# departure_board_controller.net
KiCad netlist of a schematic drawn in EasyEDA Pro
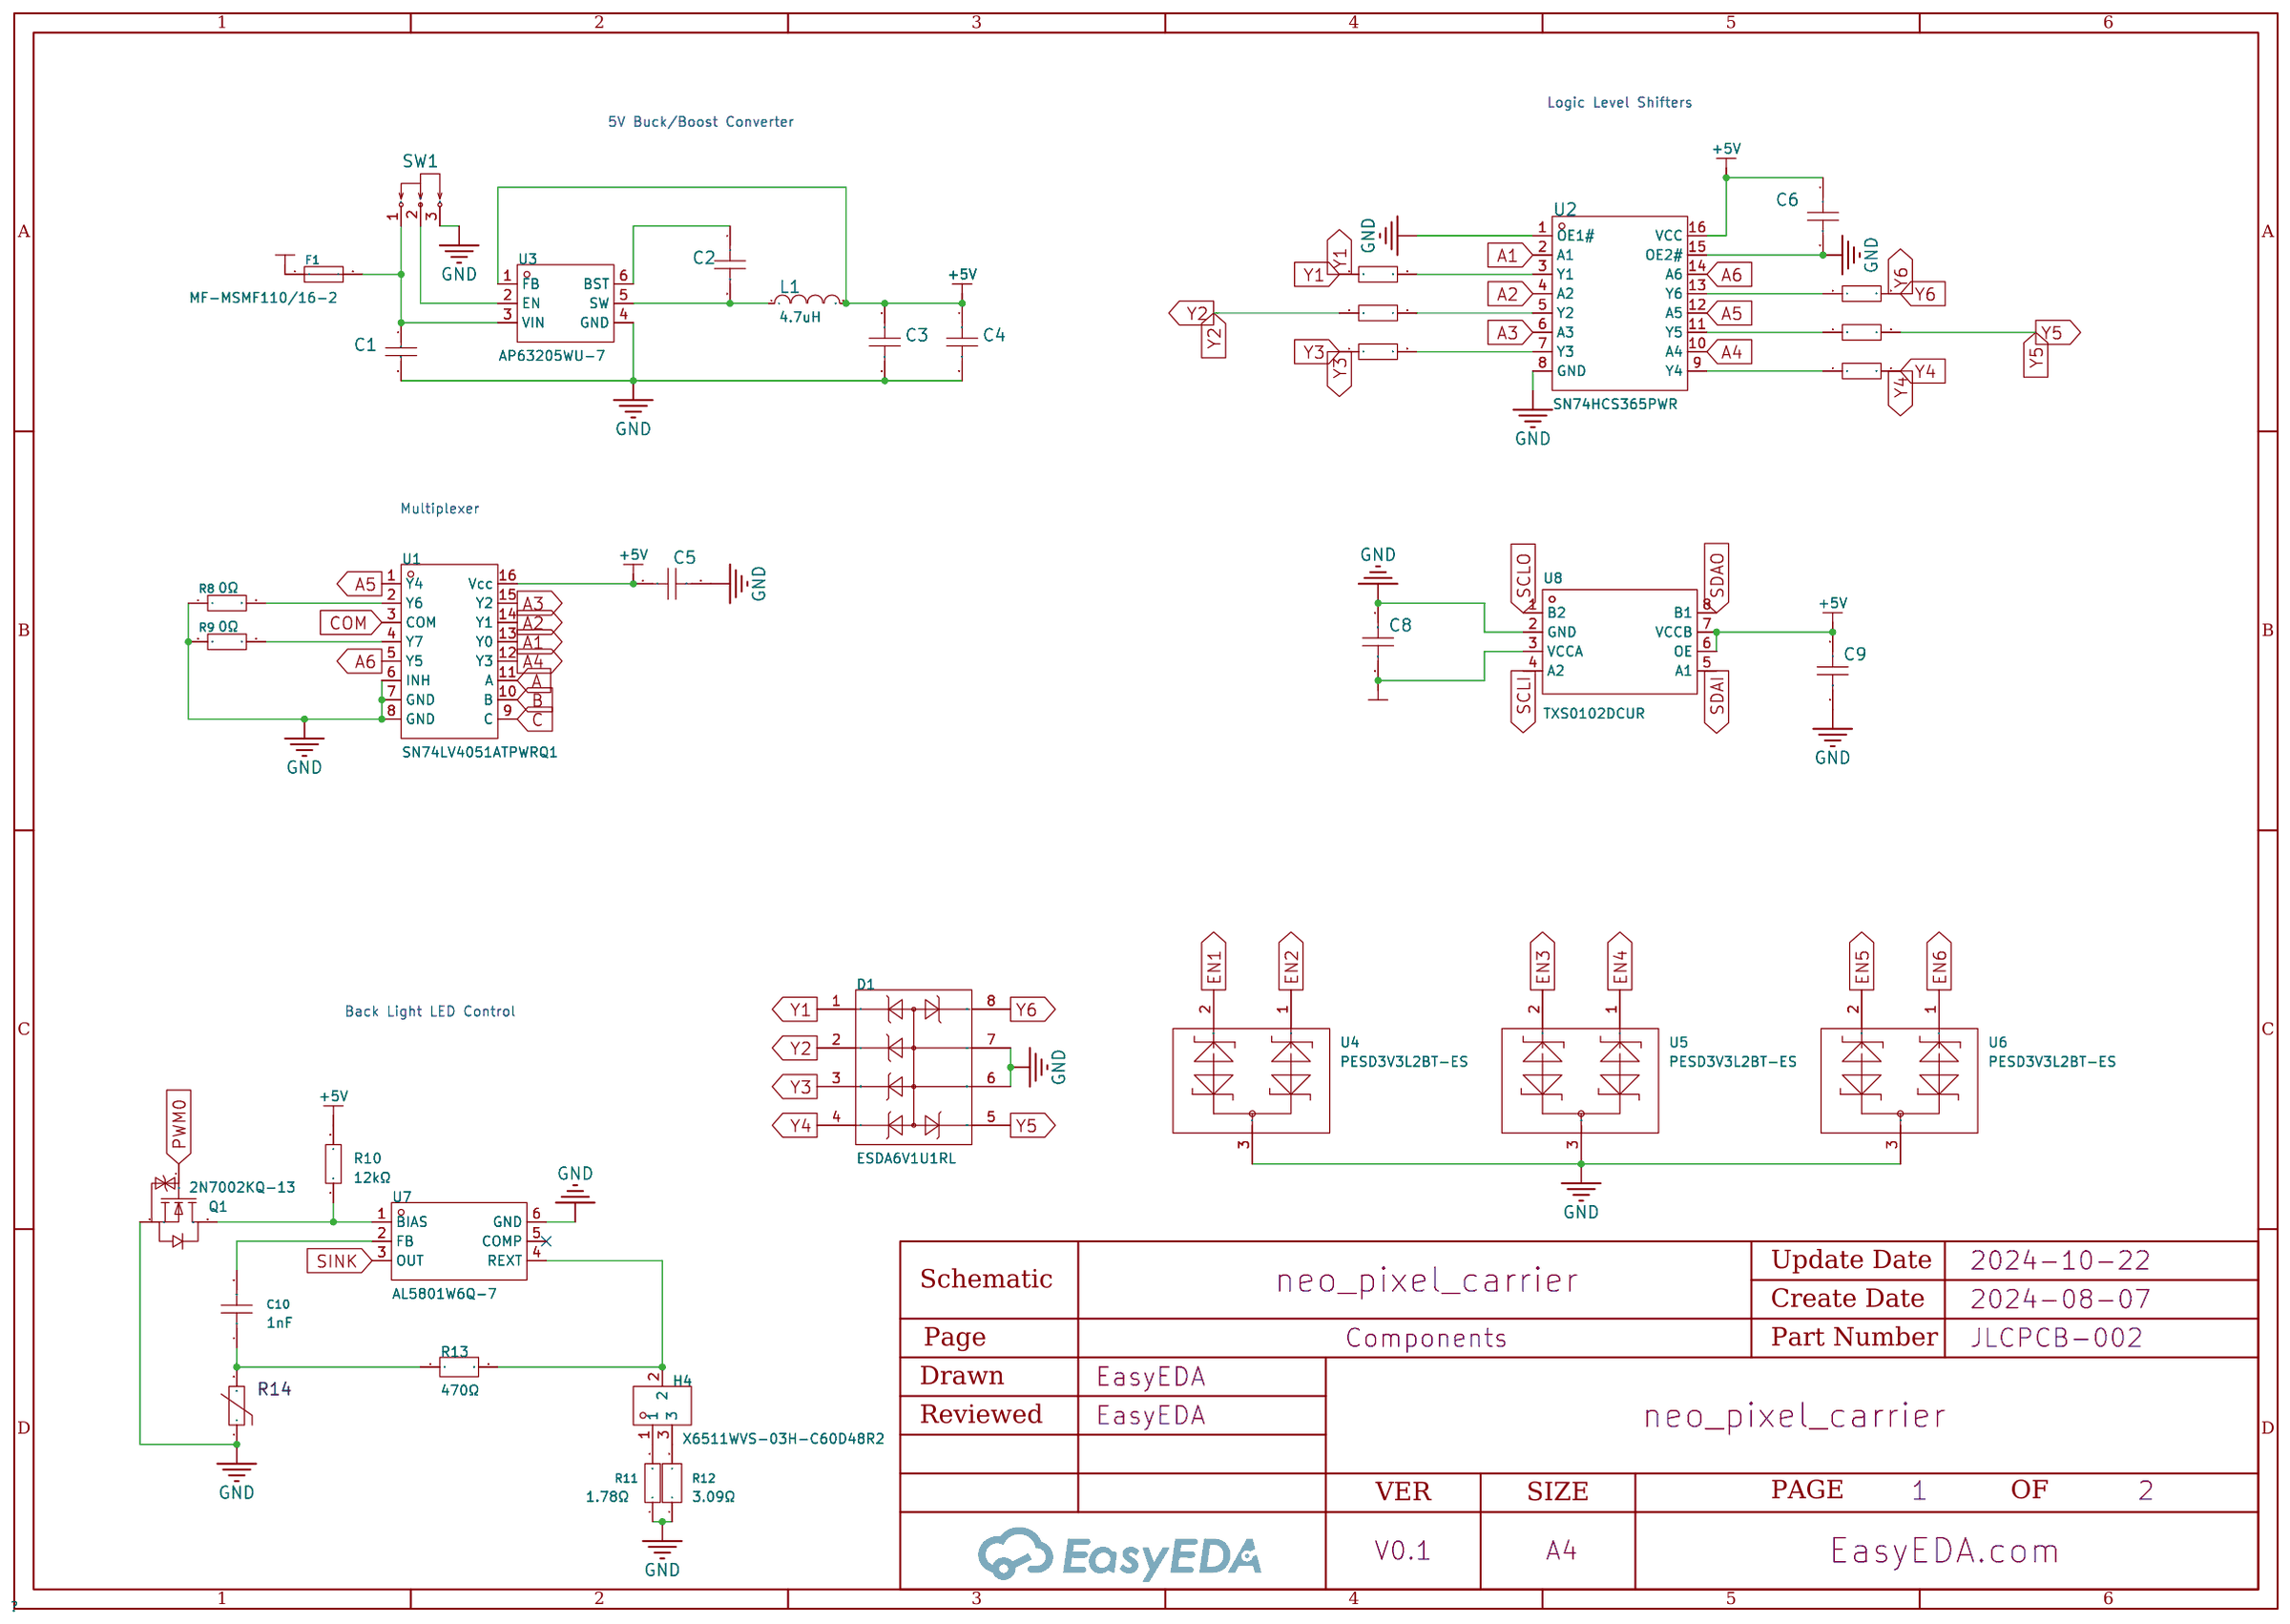
[diagram p0: Components]
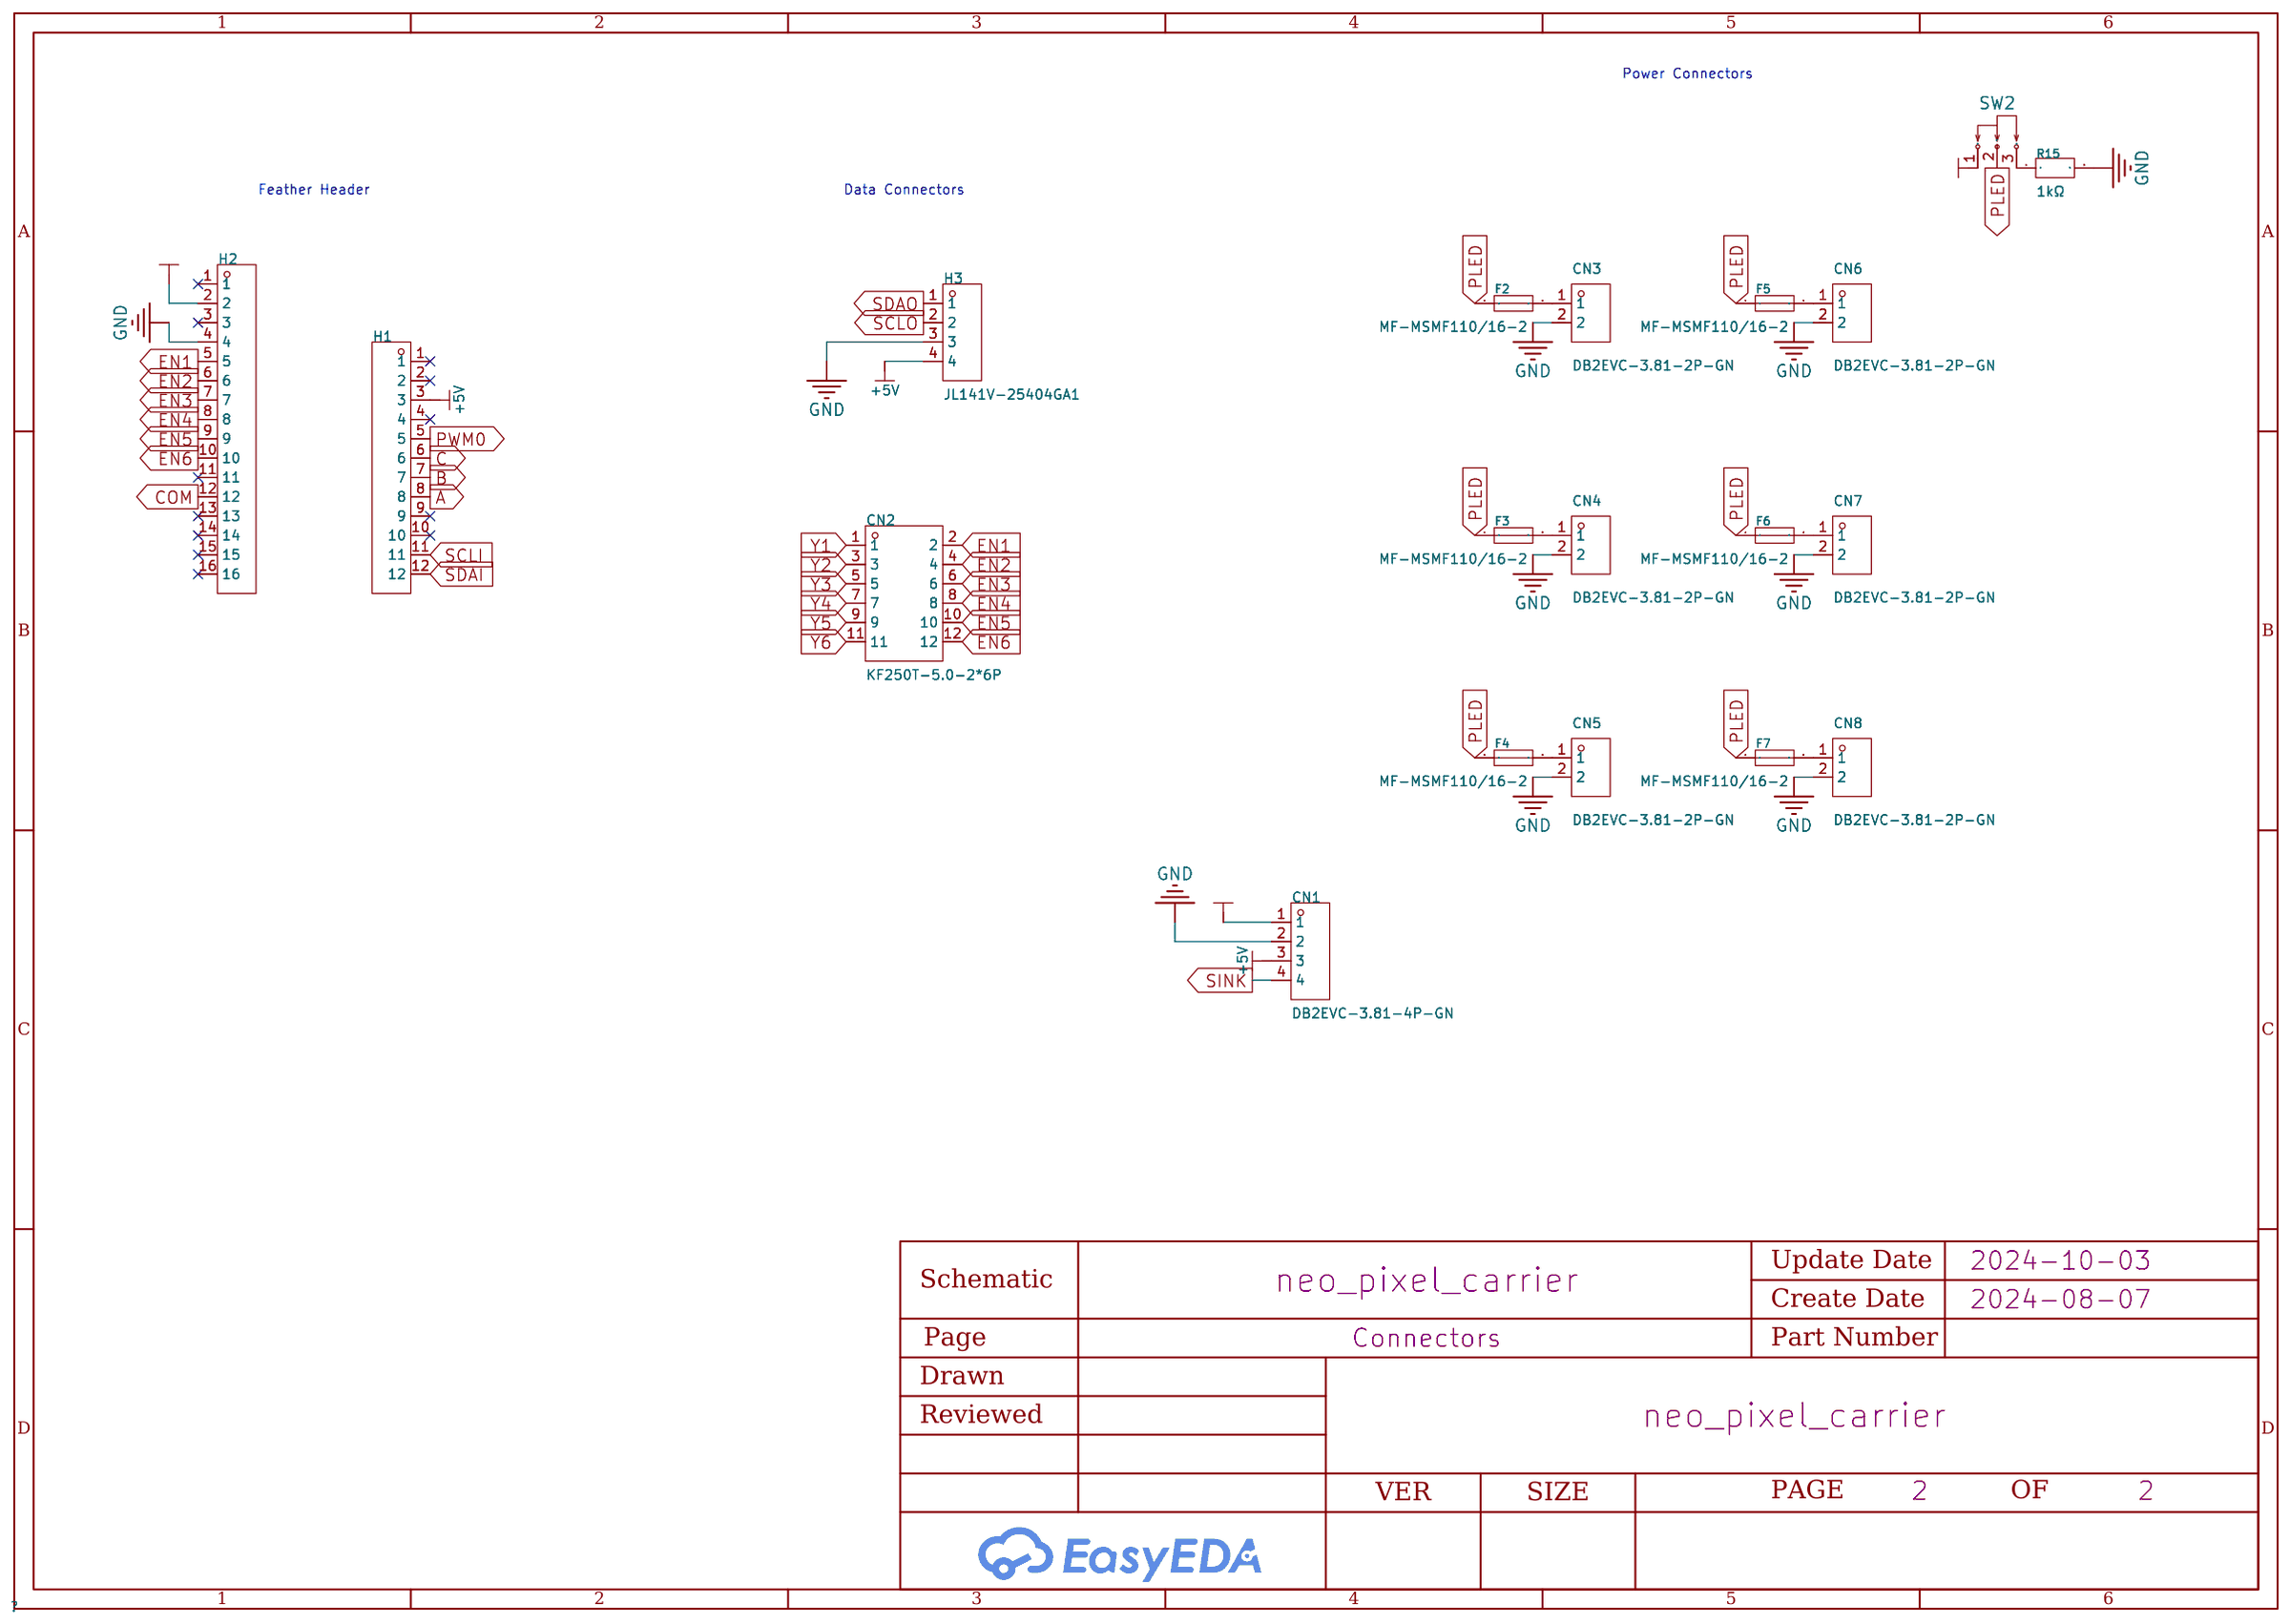
[diagram p1: Connectors]

(export (version "E")
  (design (tool "Eeschema 10.0.6"))
  (components
    (comp (ref "C1")
      (value "10uF")
      (footprint "easyedapro:C1210")
      (fields
        (field (name "Manufacturer Part") "CL32B106KAJNNNE")
        (field (name "Manufacturer") "SAMSUNG(三星)")
      )
      (libsource (lib "easyedapro") (part "CL32B106KAJNNNE"))
    )
    (comp (ref "C2")
      (value "100nF")
      (footprint "easyedapro:C1206")
      (fields (field (name "Manufacturer Part") "1206N104J500CT") (field (name "Manufacturer") "Walsin(华新科)"))
      (libsource (lib "easyedapro") (part "1206N104J500"))
    )
    (comp (ref "C3")
      (value "22uF")
      (footprint "easyedapro:C1210")
      (fields
        (field (name "Manufacturer Part") "CL32B226KAJNNNE")
        (field (name "Manufacturer") "SAMSUNG(三星)")
      )
      (libsource (lib "easyedapro") (part "CL32B226KAJNNNE"))
    )
    (comp (ref "C4")
      (value "22uF")
      (footprint "easyedapro:C1210")
      (fields
        (field (name "Manufacturer Part") "CL32B226KAJNNNE")
        (field (name "Manufacturer") "SAMSUNG(三星)")
      )
      (libsource (lib "easyedapro") (part "CL32B226KAJNNNE"))
    )
    (comp (ref "C5")
      (value "100nF")
      (footprint "easyedapro:C1206")
      (fields (field (name "Manufacturer Part") "1206N104J500CT") (field (name "Manufacturer") "Walsin(华新科)"))
      (libsource (lib "easyedapro") (part "1206N104J500"))
    )
    (comp (ref "C6")
      (value "100nF")
      (footprint "easyedapro:C1206")
      (fields (field (name "Manufacturer Part") "1206N104J500CT") (field (name "Manufacturer") "Walsin(华新科)"))
      (libsource (lib "easyedapro") (part "1206N104J500"))
    )
    (comp (ref "C8")
      (value "100nF")
      (footprint "easyedapro:C1206")
      (fields (field (name "Manufacturer Part") "1206N104J500CT") (field (name "Manufacturer") "Walsin(华新科)"))
      (libsource (lib "easyedapro") (part "1206N104J500"))
    )
    (comp (ref "C9")
      (value "100nF")
      (footprint "easyedapro:C1206")
      (fields (field (name "Manufacturer Part") "1206N104J500CT") (field (name "Manufacturer") "Walsin(华新科)"))
      (libsource (lib "easyedapro") (part "1206N104J500"))
    )
    (comp (ref "C10")
      (value "1nF")
      (footprint "easyedapro:C0402")
      (fields
        (field (name "Manufacturer Part") "GRM1555C1H102JA01D")
        (field (name "Manufacturer") "muRata(村田)")
      )
      (libsource (lib "easyedapro") (part "GRM1555C1H102JA01D"))
    )
    (comp (ref "D1")
      (value "ESDA6V1U1RL")
      (footprint "easyedapro:SO-8_L4.9-W3.9-P1.27-LS5.9-BL")
      (fields (field (name "Manufacturer") "ST(意法半导体)"))
      (libsource (lib "easyedapro") (part "ESDA6V1U1RL"))
    )
    (comp (ref "F1")
      (value "MF-MSMF110/16-2")
      (footprint "easyedapro:F1812")
      (fields (field (name "Manufacturer") "BOURNS"))
      (libsource (lib "easyedapro") (part "MF-MSMF110/16-2"))
    )
    (comp (ref "H4")
      (value "X6511WVS-03H-C60D48R2")
      (footprint "easyedapro:HDR-SMD_3P-P2.54_XKB_X6511WVS-03H-C60D48R2")
      (fields (field (name "Manufacturer") "XKB Connection(中国星坤)"))
      (libsource (lib "easyedapro") (part "X6511WVS-03H-C60D48R2"))
    )
    (comp (ref "L1")
      (value "4.7uH")
      (footprint "easyedapro:IND-SMD_L7.0-W7.0_CDRR7D45T125NP")
      (fields
        (field (name "Manufacturer Part") "CDRR7D45T125NP-4R7MC")
        (field (name "Manufacturer") "Sumida(胜美达)")
      )
      (libsource (lib "easyedapro") (part "CDRR7D45T125NP-4R7MC"))
    )
    (comp (ref "Q1")
      (value "2N7002KQ-13")
      (footprint "easyedapro:SOT-23-3_L2.9-W1.3-P1.90-LS2.4-BR")
      (fields (field (name "Manufacturer") "DIODES(美台)"))
      (libsource (lib "easyedapro") (part "2N7002KQ-13"))
    )
    (comp (ref "R1")
      (value "100Ω")
      (footprint "easyedapro:R0805")
      (fields (field (name "Manufacturer Part") "ERA6AEB101V") (field (name "Manufacturer") "PANASONIC(松下)"))
      (libsource (lib "easyedapro") (part "ERA6AEB101V"))
    )
    (comp (ref "R2")
      (value "100Ω")
      (footprint "easyedapro:R0805")
      (fields (field (name "Manufacturer Part") "ERA6AEB101V") (field (name "Manufacturer") "PANASONIC(松下)"))
      (libsource (lib "easyedapro") (part "ERA6AEB101V"))
    )
    (comp (ref "R3")
      (value "100Ω")
      (footprint "easyedapro:R0805")
      (fields (field (name "Manufacturer Part") "ERA6AEB101V") (field (name "Manufacturer") "PANASONIC(松下)"))
      (libsource (lib "easyedapro") (part "ERA6AEB101V"))
    )
    (comp (ref "R4")
      (value "100Ω")
      (footprint "easyedapro:R0805")
      (fields (field (name "Manufacturer Part") "ERA6AEB101V") (field (name "Manufacturer") "PANASONIC(松下)"))
      (libsource (lib "easyedapro") (part "ERA6AEB101V"))
    )
    (comp (ref "R5")
      (value "100Ω")
      (footprint "easyedapro:R0805")
      (fields (field (name "Manufacturer Part") "ERA6AEB101V") (field (name "Manufacturer") "PANASONIC(松下)"))
      (libsource (lib "easyedapro") (part "ERA6AEB101V"))
    )
    (comp (ref "R6")
      (value "100Ω")
      (footprint "easyedapro:R0805")
      (fields (field (name "Manufacturer Part") "ERA6AEB101V") (field (name "Manufacturer") "PANASONIC(松下)"))
      (libsource (lib "easyedapro") (part "ERA6AEB101V"))
    )
    (comp (ref "R8")
      (value "0Ω")
      (footprint "easyedapro:R0805")
      (fields (field (name "Manufacturer Part") "RTT050000FTP") (field (name "Manufacturer") "RALEC(旺诠)"))
      (libsource (lib "easyedapro") (part "RTT050000FTP"))
    )
    (comp (ref "R9")
      (value "0Ω")
      (footprint "easyedapro:R0805")
      (fields (field (name "Manufacturer Part") "RTT050000FTP") (field (name "Manufacturer") "RALEC(旺诠)"))
      (libsource (lib "easyedapro") (part "RTT050000FTP"))
    )
    (comp (ref "R10")
      (value "12kΩ")
      (footprint "easyedapro:R0805")
      (fields (field (name "Manufacturer Part") "PTFR0805B12K0N9") (field (name "Manufacturer") "RESI(开步睿思)"))
      (libsource (lib "easyedapro") (part "PTFR0805B12K0N9"))
    )
    (comp (ref "R11")
      (value "1.78Ω")
      (footprint "easyedapro:R0805")
      (fields
        (field (name "Manufacturer Part") "TR0805D1R78P0525")
        (field (name "Manufacturer") "EVER OHMS(天二科技)")
      )
      (libsource (lib "easyedapro") (part "TR0805D1R78P0525"))
    )
    (comp (ref "R12")
      (value "3.09Ω")
      (footprint "easyedapro:R0805")
      (fields (field (name "Manufacturer Part") "WR08W3R09FTL") (field (name "Manufacturer") "Walsin(华新科)"))
      (libsource (lib "easyedapro") (part "WR08W3R09FTL"))
    )
    (comp (ref "R13")
      (value "470Ω")
      (footprint "easyedapro:R0402")
      (fields (field (name "Manufacturer Part") "ERA2AEB471X") (field (name "Manufacturer") "PANASONIC(松下)"))
      (libsource (lib "easyedapro") (part "ERA2AEB471X"))
    )
    (comp (ref "R14")
      (value "10k")
      (footprint "easyedapro:R0805")
      (fields
        (field (name "Manufacturer Part") "KNTC0805/10KJ3450")
        (field (name "Manufacturer") "KUU")
        (field (name "Tolerance") "±0.5%")
      )
      (libsource (lib "easyedapro") (part "KNTC0805/10KJ3450"))
    )
    (comp (ref "SW1")
      (value "SS12D10G4 071")
      (footprint "easyedapro:SW-TH_SHOU-HAN_SS12D10G4")
      (fields (field (name "Manufacturer") "SHOU HAN(首韩)"))
      (libsource (lib "easyedapro") (part "SS12D10G4 071"))
    )
    (comp (ref "U1")
      (value "SN74LV4051ATPWRQ1")
      (footprint "easyedapro:TSSOP-16_L5.0-W4.4-P0.65-LS6.4-BL")
      (fields (field (name "Manufacturer") "TI(德州仪器)"))
      (libsource (lib "easyedapro") (part "SN74LV4051ATPWRQ1"))
    )
    (comp (ref "U2")
      (value "SN74HCS365PWR")
      (footprint "easyedapro:TSSOP-16_L5.0-W4.4-P0.65-LS6.4-BL")
      (fields (field (name "Manufacturer") "TI(德州仪器)"))
      (libsource (lib "easyedapro") (part "SN74HCS365PWR"))
    )
    (comp (ref "U3")
      (value "AP63205WU-7")
      (footprint "easyedapro:TSOT-23-6_L2.9-W1.6-P0.95-LS2.8-BL")
      (fields (field (name "Manufacturer") "DIODES(美台)"))
      (libsource (lib "easyedapro") (part "AP63205WU-7"))
    )
    (comp (ref "U4")
      (value "PESD3V3L2BT-ES")
      (footprint "easyedapro:SOT-23-3_L2.9-W1.3-P0.95-LS2.4-BR")
      (fields (field (name "Manufacturer") "ElecSuper(静芯微)"))
      (libsource (lib "easyedapro") (part "PESD3V3L2BT-ES"))
    )
    (comp (ref "U5")
      (value "PESD3V3L2BT-ES")
      (footprint "easyedapro:SOT-23-3_L2.9-W1.3-P0.95-LS2.4-BR")
      (fields (field (name "Manufacturer") "ElecSuper(静芯微)"))
      (libsource (lib "easyedapro") (part "PESD3V3L2BT-ES"))
    )
    (comp (ref "U6")
      (value "PESD3V3L2BT-ES")
      (footprint "easyedapro:SOT-23-3_L2.9-W1.3-P0.95-LS2.4-BR")
      (fields (field (name "Manufacturer") "ElecSuper(静芯微)"))
      (libsource (lib "easyedapro") (part "PESD3V3L2BT-ES"))
    )
    (comp (ref "U7")
      (value "AL5801W6Q-7")
      (footprint "easyedapro:SOT-26-6_L3.0-W1.6-P0.95-LS2.8-BL")
      (fields (field (name "Manufacturer") "DIODES(美台)"))
      (libsource (lib "easyedapro") (part "AL5801W6Q-7"))
    )
    (comp (ref "U8")
      (value "TXS0102DCUR")
      (footprint "easyedapro:VSON8_L2.0-W2.3-P0.50-LS3.1-BL")
      (fields (field (name "Manufacturer") "TI(德州仪器)"))
      (libsource (lib "easyedapro") (part "TXS0102DCUR"))
    )
    (comp (ref "CN1")
      (value "DB2EVC-3.81-4P-GN")
      (footprint "easyedapro:CONN-TH_4P-P3.81_DB2EVC-3.81-4P")
      (fields (field (name "Manufacturer") "DORABO(地博电气)"))
      (libsource (lib "easyedapro") (part "DB2EVC-3.81-4P"))
    )
    (comp (ref "CN2")
      (value "KF250T-5.0-2*6P")
      (footprint "easyedapro:CONN-TH_KF250T-5.0-2X6P")
      (fields (field (name "Manufacturer") "KEFA(科发)"))
      (libsource (lib "easyedapro") (part "KF250T-5.0-2*6P"))
    )
    (comp (ref "CN3")
      (value "DB2EVC-3.81-2P-GN")
      (footprint "easyedapro:CONN-TH_2P-P3.81_DB2EVC-3.81-2P-BK")
      (fields (field (name "Manufacturer") "DORABO(地博电气)"))
      (libsource (lib "easyedapro") (part "DB2EVC-3.81-2P"))
    )
    (comp (ref "CN4")
      (value "DB2EVC-3.81-2P-GN")
      (footprint "easyedapro:CONN-TH_2P-P3.81_DB2EVC-3.81-2P-BK")
      (fields (field (name "Manufacturer") "DORABO(地博电气)"))
      (libsource (lib "easyedapro") (part "DB2EVC-3.81-2P"))
    )
    (comp (ref "CN5")
      (value "DB2EVC-3.81-2P-GN")
      (footprint "easyedapro:CONN-TH_2P-P3.81_DB2EVC-3.81-2P-BK")
      (fields (field (name "Manufacturer") "DORABO(地博电气)"))
      (libsource (lib "easyedapro") (part "DB2EVC-3.81-2P"))
    )
    (comp (ref "CN6")
      (value "DB2EVC-3.81-2P-GN")
      (footprint "easyedapro:CONN-TH_2P-P3.81_DB2EVC-3.81-2P-BK")
      (fields (field (name "Manufacturer") "DORABO(地博电气)"))
      (libsource (lib "easyedapro") (part "DB2EVC-3.81-2P"))
    )
    (comp (ref "CN7")
      (value "DB2EVC-3.81-2P-GN")
      (footprint "easyedapro:CONN-TH_2P-P3.81_DB2EVC-3.81-2P-BK")
      (fields (field (name "Manufacturer") "DORABO(地博电气)"))
      (libsource (lib "easyedapro") (part "DB2EVC-3.81-2P"))
    )
    (comp (ref "CN8")
      (value "DB2EVC-3.81-2P-GN")
      (footprint "easyedapro:CONN-TH_2P-P3.81_DB2EVC-3.81-2P-BK")
      (fields (field (name "Manufacturer") "DORABO(地博电气)"))
      (libsource (lib "easyedapro") (part "DB2EVC-3.81-2P"))
    )
    (comp (ref "F2")
      (value "MF-MSMF110/16-2")
      (footprint "easyedapro:F1812")
      (fields (field (name "Manufacturer") "BOURNS"))
      (libsource (lib "easyedapro") (part "MF-MSMF110/16-2"))
    )
    (comp (ref "F3")
      (value "MF-MSMF110/16-2")
      (footprint "easyedapro:F1812")
      (fields (field (name "Manufacturer") "BOURNS"))
      (libsource (lib "easyedapro") (part "MF-MSMF110/16-2"))
    )
    (comp (ref "F4")
      (value "MF-MSMF110/16-2")
      (footprint "easyedapro:F1812")
      (fields (field (name "Manufacturer") "BOURNS"))
      (libsource (lib "easyedapro") (part "MF-MSMF110/16-2"))
    )
    (comp (ref "F5")
      (value "MF-MSMF110/16-2")
      (footprint "easyedapro:F1812")
      (fields (field (name "Manufacturer") "BOURNS"))
      (libsource (lib "easyedapro") (part "MF-MSMF110/16-2"))
    )
    (comp (ref "F6")
      (value "MF-MSMF110/16-2")
      (footprint "easyedapro:F1812")
      (fields (field (name "Manufacturer") "BOURNS"))
      (libsource (lib "easyedapro") (part "MF-MSMF110/16-2"))
    )
    (comp (ref "F7")
      (value "MF-MSMF110/16-2")
      (footprint "easyedapro:F1812")
      (fields (field (name "Manufacturer") "BOURNS"))
      (libsource (lib "easyedapro") (part "MF-MSMF110/16-2"))
    )
    (comp (ref "H1")
      (value "A2541HWV-12P")
      (footprint "easyedapro:HDR-TH_12P-P2.54-V-F")
      (fields (field (name "Manufacturer") "CJT(长江连接器)"))
      (libsource (lib "easyedapro") (part "PM2.54-1*12"))
    )
    (comp (ref "H2")
      (value "ZX-PM2.54-1-16PY")
      (footprint "easyedapro:HDR-TH_16P-P2.54-V-F-A")
      (fields (field (name "Manufacturer") "Megastar(兆星)"))
      (libsource (lib "easyedapro") (part "PM254-1-16-Z-8.5"))
    )
    (comp (ref "H3")
      (value "JL141V-25404GA1")
      (footprint "easyedapro:CONN-TH_4P-P2.54_JILN_JL141V-25404GA1")
      (fields (field (name "Manufacturer") "JILN(锦凌)"))
      (libsource (lib "easyedapro") (part "JL141V-25404GA1"))
    )
    (comp (ref "R15")
      (value "1kΩ")
      (footprint "easyedapro:R0805")
      (fields
        (field (name "Manufacturer Part") "ERJ-HP6F1001V")
        (field (name "Manufacturer") "PANASONIC(松下)")
      )
      (libsource (lib "easyedapro") (part "ERJ-HP6F1001V"))
    )
    (comp (ref "SW2")
      (value "SS12D10G4 071")
      (footprint "easyedapro:SW-TH_SHOU-HAN_SS12D10G4")
      (fields (field (name "Manufacturer") "SHOU HAN(首韩)"))
      (libsource (lib "easyedapro") (part "SS12D10G4 071"))
    )
  )
  (nets
    (net (code "1") (name "+3.3V") (class "Default")
      (node (ref "C8") (pin "2") (pinfunction "2_2") (pintype "unspecified"))
      (node (ref "H2") (pin "2") (pinfunction "2_2") (pintype "unspecified"))
      (node (ref "U8") (pin "3") (pinfunction "VCCA_3") (pintype "unspecified"))
    )
    (net (code "2") (name "+5V") (class "Default")
      (node (ref "C3") (pin "1") (pinfunction "1_1") (pintype "unspecified"))
      (node (ref "C4") (pin "1") (pinfunction "1_1") (pintype "unspecified"))
      (node (ref "C5") (pin "1") (pinfunction "1_1") (pintype "unspecified"))
      (node (ref "C6") (pin "1") (pinfunction "1_1") (pintype "unspecified"))
      (node (ref "C9") (pin "1") (pinfunction "1_1") (pintype "unspecified"))
      (node (ref "CN1") (pin "3") (pinfunction "3_3") (pintype "unspecified"))
      (node (ref "H1") (pin "3") (pinfunction "3_3") (pintype "unspecified"))
      (node (ref "H3") (pin "4") (pinfunction "4_4") (pintype "unspecified"))
      (node (ref "L1") (pin "2") (pinfunction "2_2") (pintype "input"))
      (node (ref "R10") (pin "2") (pinfunction "2_2") (pintype "unspecified"))
      (node (ref "U1") (pin "16") (pinfunction "Vcc_16") (pintype "unspecified"))
      (node (ref "U2") (pin "16") (pinfunction "VCC_16") (pintype "input"))
      (node (ref "U3") (pin "1") (pinfunction "FB_1") (pintype "input"))
      (node (ref "U8") (pin "6") (pinfunction "OE_6") (pintype "unspecified"))
      (node (ref "U8") (pin "7") (pinfunction "VCCB_7") (pintype "unspecified"))
    )
    (net (code "3") (name "A") (class "Default")
      (node (ref "H1") (pin "8") (pinfunction "8_8") (pintype "unspecified"))
      (node (ref "U1") (pin "11") (pinfunction "A_11") (pintype "unspecified"))
    )
    (net (code "4") (name "A1") (class "Default")
      (node (ref "U1") (pin "13") (pinfunction "Y0_13") (pintype "unspecified"))
      (node (ref "U2") (pin "2") (pinfunction "A1_2") (pintype "input"))
    )
    (net (code "5") (name "A2") (class "Default")
      (node (ref "U1") (pin "14") (pinfunction "Y1_14") (pintype "unspecified"))
      (node (ref "U2") (pin "4") (pinfunction "A2_4") (pintype "input"))
    )
    (net (code "6") (name "A3") (class "Default")
      (node (ref "U1") (pin "15") (pinfunction "Y2_15") (pintype "unspecified"))
      (node (ref "U2") (pin "6") (pinfunction "A3_6") (pintype "input"))
    )
    (net (code "7") (name "A4") (class "Default")
      (node (ref "U1") (pin "12") (pinfunction "Y3_12") (pintype "unspecified"))
      (node (ref "U2") (pin "10") (pinfunction "A4_10") (pintype "input"))
    )
    (net (code "8") (name "A5") (class "Default")
      (node (ref "U1") (pin "1") (pinfunction "Y4_1") (pintype "unspecified"))
      (node (ref "U2") (pin "12") (pinfunction "A5_12") (pintype "input"))
    )
    (net (code "9") (name "A6") (class "Default")
      (node (ref "U1") (pin "5") (pinfunction "Y5_5") (pintype "unspecified"))
      (node (ref "U2") (pin "14") (pinfunction "A6_14") (pintype "input"))
    )
    (net (code "10") (name "B") (class "Default")
      (node (ref "H1") (pin "7") (pinfunction "7_7") (pintype "unspecified"))
      (node (ref "U1") (pin "10") (pinfunction "B_10") (pintype "unspecified"))
    )
    (net (code "11") (name "C") (class "Default")
      (node (ref "H1") (pin "6") (pinfunction "6_6") (pintype "unspecified"))
      (node (ref "U1") (pin "9") (pinfunction "C_9") (pintype "unspecified"))
    )
    (net (code "12") (name "COM") (class "Default")
      (node (ref "H2") (pin "12") (pinfunction "12_12") (pintype "unspecified"))
      (node (ref "U1") (pin "3") (pinfunction "COM_3") (pintype "unspecified"))
    )
    (net (code "13") (name "EN1") (class "Default")
      (node (ref "CN2") (pin "2") (pinfunction "2_2") (pintype "unspecified"))
      (node (ref "H2") (pin "5") (pinfunction "5_5") (pintype "unspecified"))
      (node (ref "U4") (pin "2") (pinfunction "2_2") (pintype "input"))
    )
    (net (code "14") (name "EN2") (class "Default")
      (node (ref "CN2") (pin "4") (pinfunction "4_4") (pintype "unspecified"))
      (node (ref "H2") (pin "6") (pinfunction "6_6") (pintype "unspecified"))
      (node (ref "U4") (pin "1") (pinfunction "1_1") (pintype "input"))
    )
    (net (code "15") (name "EN3") (class "Default")
      (node (ref "CN2") (pin "6") (pinfunction "6_6") (pintype "unspecified"))
      (node (ref "H2") (pin "7") (pinfunction "7_7") (pintype "unspecified"))
      (node (ref "U5") (pin "2") (pinfunction "2_2") (pintype "input"))
    )
    (net (code "16") (name "EN4") (class "Default")
      (node (ref "CN2") (pin "8") (pinfunction "8_8") (pintype "unspecified"))
      (node (ref "H2") (pin "8") (pinfunction "8_8") (pintype "unspecified"))
      (node (ref "U5") (pin "1") (pinfunction "1_1") (pintype "input"))
    )
    (net (code "17") (name "EN5") (class "Default")
      (node (ref "CN2") (pin "10") (pinfunction "10_10") (pintype "unspecified"))
      (node (ref "H2") (pin "9") (pinfunction "9_9") (pintype "unspecified"))
      (node (ref "U6") (pin "2") (pinfunction "2_2") (pintype "input"))
    )
    (net (code "18") (name "EN6") (class "Default")
      (node (ref "CN2") (pin "12") (pinfunction "12_12") (pintype "unspecified"))
      (node (ref "H2") (pin "10") (pinfunction "10_10") (pintype "unspecified"))
      (node (ref "U6") (pin "1") (pinfunction "1_1") (pintype "input"))
    )
    (net (code "19") (name "GND") (class "Default")
      (node (ref "C1") (pin "2") (pinfunction "2_2") (pintype "input"))
      (node (ref "C3") (pin "2") (pinfunction "2_2") (pintype "unspecified"))
      (node (ref "C4") (pin "2") (pinfunction "2_2") (pintype "unspecified"))
      (node (ref "C5") (pin "2") (pinfunction "2_2") (pintype "unspecified"))
      (node (ref "C6") (pin "2") (pinfunction "2_2") (pintype "unspecified"))
      (node (ref "C8") (pin "1") (pinfunction "1_1") (pintype "unspecified"))
      (node (ref "C9") (pin "2") (pinfunction "2_2") (pintype "unspecified"))
      (node (ref "CN1") (pin "2") (pinfunction "2_2") (pintype "unspecified"))
      (node (ref "CN3") (pin "2") (pinfunction "2_2") (pintype "unspecified"))
      (node (ref "CN4") (pin "2") (pinfunction "2_2") (pintype "unspecified"))
      (node (ref "CN5") (pin "2") (pinfunction "2_2") (pintype "unspecified"))
      (node (ref "CN6") (pin "2") (pinfunction "2_2") (pintype "unspecified"))
      (node (ref "CN7") (pin "2") (pinfunction "2_2") (pintype "unspecified"))
      (node (ref "CN8") (pin "2") (pinfunction "2_2") (pintype "unspecified"))
      (node (ref "D1") (pin "6") (pinfunction "GND_6") (pintype "unspecified"))
      (node (ref "D1") (pin "7") (pinfunction "GND_7") (pintype "unspecified"))
      (node (ref "H2") (pin "4") (pinfunction "4_4") (pintype "unspecified"))
      (node (ref "H3") (pin "3") (pinfunction "3_3") (pintype "unspecified"))
      (node (ref "Q1") (pin "2") (pinfunction "S_2") (pintype "unspecified"))
      (node (ref "R11") (pin "1") (pinfunction "1_1") (pintype "input"))
      (node (ref "R12") (pin "1") (pinfunction "1_1") (pintype "input"))
      (node (ref "R14") (pin "1") (pinfunction "1_1") (pintype "unspecified"))
      (node (ref "R15") (pin "2") (pinfunction "2_2") (pintype "input"))
      (node (ref "R8") (pin "1") (pinfunction "1_1") (pintype "input"))
      (node (ref "R9") (pin "1") (pinfunction "1_1") (pintype "input"))
      (node (ref "SW1") (pin "3") (pinfunction "3_3") (pintype "input"))
      (node (ref "U1") (pin "6") (pinfunction "INH_6") (pintype "unspecified"))
      (node (ref "U1") (pin "7") (pinfunction "GND_7") (pintype "unspecified"))
      (node (ref "U1") (pin "8") (pinfunction "GND_8") (pintype "unspecified"))
      (node (ref "U2") (pin "1") (pinfunction "OE1#_1") (pintype "input"))
      (node (ref "U2") (pin "15") (pinfunction "OE2#_15") (pintype "input"))
      (node (ref "U2") (pin "8") (pinfunction "GND_8") (pintype "input"))
      (node (ref "U3") (pin "4") (pinfunction "GND_4") (pintype "input"))
      (node (ref "U4") (pin "3") (pinfunction "3_3") (pintype "input"))
      (node (ref "U5") (pin "3") (pinfunction "3_3") (pintype "input"))
      (node (ref "U6") (pin "3") (pinfunction "3_3") (pintype "input"))
      (node (ref "U7") (pin "6") (pinfunction "GND_6") (pintype "input"))
      (node (ref "U8") (pin "2") (pinfunction "GND_2") (pintype "unspecified"))
    )
    (net (code "20") (name "Net-(C10-Pad1)") (class "Default")
      (node (ref "C10") (pin "1") (pinfunction "1_1") (pintype "input"))
      (node (ref "R13") (pin "1") (pinfunction "1_1") (pintype "unspecified"))
      (node (ref "R14") (pin "2") (pinfunction "2_2") (pintype "unspecified"))
    )
    (net (code "21") (name "Net-(CN3-Pad1)") (class "Default")
      (node (ref "CN3") (pin "1") (pinfunction "1_1") (pintype "unspecified"))
      (node (ref "F2") (pin "2") (pinfunction "2_2") (pintype "input"))
    )
    (net (code "22") (name "Net-(CN4-Pad1)") (class "Default")
      (node (ref "CN4") (pin "1") (pinfunction "1_1") (pintype "unspecified"))
      (node (ref "F3") (pin "2") (pinfunction "2_2") (pintype "input"))
    )
    (net (code "23") (name "Net-(CN5-Pad1)") (class "Default")
      (node (ref "CN5") (pin "1") (pinfunction "1_1") (pintype "unspecified"))
      (node (ref "F4") (pin "2") (pinfunction "2_2") (pintype "input"))
    )
    (net (code "24") (name "Net-(CN6-Pad1)") (class "Default")
      (node (ref "CN6") (pin "1") (pinfunction "1_1") (pintype "unspecified"))
      (node (ref "F5") (pin "2") (pinfunction "2_2") (pintype "input"))
    )
    (net (code "25") (name "Net-(CN7-Pad1)") (class "Default")
      (node (ref "CN7") (pin "1") (pinfunction "1_1") (pintype "unspecified"))
      (node (ref "F6") (pin "2") (pinfunction "2_2") (pintype "input"))
    )
    (net (code "26") (name "Net-(CN8-Pad1)") (class "Default")
      (node (ref "CN8") (pin "1") (pinfunction "1_1") (pintype "unspecified"))
      (node (ref "F7") (pin "2") (pinfunction "2_2") (pintype "input"))
    )
    (net (code "27") (name "Net-(H4-Pad1)") (class "Default")
      (node (ref "H4") (pin "1") (pinfunction "1_1") (pintype "unspecified"))
      (node (ref "R11") (pin "2") (pinfunction "2_2") (pintype "input"))
    )
    (net (code "28") (name "Net-(H4-Pad3)") (class "Default")
      (node (ref "H4") (pin "3") (pinfunction "3_3") (pintype "unspecified"))
      (node (ref "R12") (pin "2") (pinfunction "2_2") (pintype "input"))
    )
    (net (code "29") (name "Net-(Q1-D)") (class "Default")
      (node (ref "Q1") (pin "3") (pinfunction "D_3") (pintype "unspecified"))
      (node (ref "R10") (pin "1") (pinfunction "1_1") (pintype "unspecified"))
      (node (ref "U7") (pin "1") (pinfunction "BIAS_1") (pintype "input"))
    )
    (net (code "30") (name "Net-(R15-Pad1)") (class "Default")
      (node (ref "R15") (pin "1") (pinfunction "1_1") (pintype "input"))
      (node (ref "SW2") (pin "3") (pinfunction "3_3") (pintype "input"))
    )
    (net (code "31") (name "Net-(U1-Y6)") (class "Default")
      (node (ref "R8") (pin "2") (pinfunction "2_2") (pintype "input"))
      (node (ref "U1") (pin "2") (pinfunction "Y6_2") (pintype "unspecified"))
    )
    (net (code "32") (name "Net-(U1-Y7)") (class "Default")
      (node (ref "R9") (pin "2") (pinfunction "2_2") (pintype "input"))
      (node (ref "U1") (pin "4") (pinfunction "Y7_4") (pintype "unspecified"))
    )
    (net (code "33") (name "Net-(U2-Y1)") (class "Default")
      (node (ref "R1") (pin "2") (pinfunction "2_2") (pintype "input"))
      (node (ref "U2") (pin "3") (pinfunction "Y1_3") (pintype "input"))
    )
    (net (code "34") (name "Net-(U2-Y2)") (class "Default")
      (node (ref "R2") (pin "2") (pinfunction "2_2") (pintype "input"))
      (node (ref "U2") (pin "5") (pinfunction "Y2_5") (pintype "input"))
    )
    (net (code "35") (name "Net-(U2-Y3)") (class "Default")
      (node (ref "R3") (pin "2") (pinfunction "2_2") (pintype "input"))
      (node (ref "U2") (pin "7") (pinfunction "Y3_7") (pintype "input"))
    )
    (net (code "36") (name "Net-(U2-Y4)") (class "Default")
      (node (ref "R4") (pin "1") (pinfunction "1_1") (pintype "input"))
      (node (ref "U2") (pin "9") (pinfunction "Y4_9") (pintype "input"))
    )
    (net (code "37") (name "Net-(U2-Y5)") (class "Default")
      (node (ref "R5") (pin "1") (pinfunction "1_1") (pintype "input"))
      (node (ref "U2") (pin "11") (pinfunction "Y5_11") (pintype "input"))
    )
    (net (code "38") (name "Net-(U2-Y6)") (class "Default")
      (node (ref "R6") (pin "1") (pinfunction "1_1") (pintype "input"))
      (node (ref "U2") (pin "13") (pinfunction "Y6_13") (pintype "input"))
    )
    (net (code "39") (name "Net-(U3-BST)") (class "Default")
      (node (ref "C2") (pin "1") (pinfunction "1_1") (pintype "unspecified"))
      (node (ref "U3") (pin "6") (pinfunction "BST_6") (pintype "input"))
    )
    (net (code "40") (name "Net-(U3-EN)") (class "Default")
      (node (ref "SW1") (pin "2") (pinfunction "2_2") (pintype "input"))
      (node (ref "U3") (pin "2") (pinfunction "EN_2") (pintype "input"))
    )
    (net (code "41") (name "Net-(U3-SW)") (class "Default")
      (node (ref "C2") (pin "2") (pinfunction "2_2") (pintype "unspecified"))
      (node (ref "L1") (pin "1") (pinfunction "1_1") (pintype "input"))
      (node (ref "U3") (pin "5") (pinfunction "SW_5") (pintype "input"))
    )
    (net (code "42") (name "Net-(U3-VIN)") (class "Default")
      (node (ref "C1") (pin "1") (pinfunction "1_1") (pintype "input"))
      (node (ref "F1") (pin "2") (pinfunction "2_2") (pintype "input"))
      (node (ref "SW1") (pin "1") (pinfunction "1_1") (pintype "input"))
      (node (ref "U3") (pin "3") (pinfunction "VIN_3") (pintype "input"))
    )
    (net (code "43") (name "Net-(U7-FB)") (class "Default")
      (node (ref "C10") (pin "2") (pinfunction "2_2") (pintype "input"))
      (node (ref "U7") (pin "2") (pinfunction "FB_2") (pintype "input"))
    )
    (net (code "44") (name "Net-(U7-REXT)") (class "Default")
      (node (ref "H4") (pin "2") (pinfunction "2_2") (pintype "unspecified"))
      (node (ref "R13") (pin "2") (pinfunction "2_2") (pintype "unspecified"))
      (node (ref "U7") (pin "4") (pinfunction "REXT_4") (pintype "input"))
    )
    (net (code "45") (name "PLED") (class "Default")
      (node (ref "F2") (pin "1") (pinfunction "1_1") (pintype "input"))
      (node (ref "F3") (pin "1") (pinfunction "1_1") (pintype "input"))
      (node (ref "F4") (pin "1") (pinfunction "1_1") (pintype "input"))
      (node (ref "F5") (pin "1") (pinfunction "1_1") (pintype "input"))
      (node (ref "F6") (pin "1") (pinfunction "1_1") (pintype "input"))
      (node (ref "F7") (pin "1") (pinfunction "1_1") (pintype "input"))
      (node (ref "SW2") (pin "2") (pinfunction "2_2") (pintype "input"))
    )
    (net (code "46") (name "PWM0") (class "Default")
      (node (ref "H1") (pin "5") (pinfunction "5_5") (pintype "unspecified"))
      (node (ref "Q1") (pin "1") (pinfunction "G_1") (pintype "unspecified"))
    )
    (net (code "47") (name "SCLI") (class "Default")
      (node (ref "H1") (pin "11") (pinfunction "11_11") (pintype "unspecified"))
      (node (ref "U8") (pin "4") (pinfunction "A2_4") (pintype "unspecified"))
    )
    (net (code "48") (name "SCLO") (class "Default")
      (node (ref "H3") (pin "2") (pinfunction "2_2") (pintype "unspecified"))
      (node (ref "U8") (pin "1") (pinfunction "B2_1") (pintype "unspecified"))
    )
    (net (code "49") (name "SDAI") (class "Default")
      (node (ref "H1") (pin "12") (pinfunction "12_12") (pintype "unspecified"))
      (node (ref "U8") (pin "5") (pinfunction "A1_5") (pintype "unspecified"))
    )
    (net (code "50") (name "SDAO") (class "Default")
      (node (ref "H3") (pin "1") (pinfunction "1_1") (pintype "unspecified"))
      (node (ref "U8") (pin "8") (pinfunction "B1_8") (pintype "unspecified"))
    )
    (net (code "51") (name "SINK") (class "Default")
      (node (ref "CN1") (pin "4") (pinfunction "4_4") (pintype "unspecified"))
      (node (ref "U7") (pin "3") (pinfunction "OUT_3") (pintype "input"))
    )
    (net (code "52") (name "VCC") (class "Default")
      (node (ref "CN1") (pin "1") (pinfunction "1_1") (pintype "unspecified"))
      (node (ref "F1") (pin "1") (pinfunction "1_1") (pintype "input"))
      (node (ref "SW2") (pin "1") (pinfunction "1_1") (pintype "input"))
    )
    (net (code "53") (name "Y1") (class "Default")
      (node (ref "CN2") (pin "1") (pinfunction "1_1") (pintype "unspecified"))
      (node (ref "D1") (pin "1") (pinfunction "I/O1_1") (pintype "unspecified"))
      (node (ref "R1") (pin "1") (pinfunction "1_1") (pintype "input"))
    )
    (net (code "54") (name "Y2") (class "Default")
      (node (ref "CN2") (pin "3") (pinfunction "3_3") (pintype "unspecified"))
      (node (ref "D1") (pin "2") (pinfunction "I/O2_2") (pintype "unspecified"))
      (node (ref "R2") (pin "1") (pinfunction "1_1") (pintype "input"))
    )
    (net (code "55") (name "Y3") (class "Default")
      (node (ref "CN2") (pin "5") (pinfunction "5_5") (pintype "unspecified"))
      (node (ref "D1") (pin "3") (pinfunction "I/O3_3") (pintype "unspecified"))
      (node (ref "R3") (pin "1") (pinfunction "1_1") (pintype "input"))
    )
    (net (code "56") (name "Y4") (class "Default")
      (node (ref "CN2") (pin "7") (pinfunction "7_7") (pintype "unspecified"))
      (node (ref "D1") (pin "4") (pinfunction "I/O4_4") (pintype "unspecified"))
      (node (ref "R4") (pin "2") (pinfunction "2_2") (pintype "input"))
    )
    (net (code "57") (name "Y5") (class "Default")
      (node (ref "CN2") (pin "9") (pinfunction "9_9") (pintype "unspecified"))
      (node (ref "D1") (pin "5") (pinfunction "I/O5_5") (pintype "unspecified"))
      (node (ref "R5") (pin "2") (pinfunction "2_2") (pintype "input"))
    )
    (net (code "58") (name "Y6") (class "Default")
      (node (ref "CN2") (pin "11") (pinfunction "11_11") (pintype "unspecified"))
      (node (ref "D1") (pin "8") (pinfunction "I/O6_8") (pintype "unspecified"))
      (node (ref "R6") (pin "2") (pinfunction "2_2") (pintype "input"))
    )
    (net (code "59") (name "unconnected-(H1-Pad1)") (class "Default")
      (node (ref "H1") (pin "1") (pinfunction "1_1") (pintype "unspecified+no_connect"))
    )
    (net (code "60") (name "unconnected-(H1-Pad2)") (class "Default")
      (node (ref "H1") (pin "2") (pinfunction "2_2") (pintype "unspecified+no_connect"))
    )
    (net (code "61") (name "unconnected-(H1-Pad4)") (class "Default")
      (node (ref "H1") (pin "4") (pinfunction "4_4") (pintype "unspecified+no_connect"))
    )
    (net (code "62") (name "unconnected-(H1-Pad9)") (class "Default")
      (node (ref "H1") (pin "9") (pinfunction "9_9") (pintype "unspecified+no_connect"))
    )
    (net (code "63") (name "unconnected-(H1-Pad10)") (class "Default")
      (node (ref "H1") (pin "10") (pinfunction "10_10") (pintype "unspecified+no_connect"))
    )
    (net (code "64") (name "unconnected-(H2-Pad1)") (class "Default")
      (node (ref "H2") (pin "1") (pinfunction "1_1") (pintype "unspecified+no_connect"))
    )
    (net (code "65") (name "unconnected-(H2-Pad3)") (class "Default")
      (node (ref "H2") (pin "3") (pinfunction "3_3") (pintype "unspecified+no_connect"))
    )
    (net (code "66") (name "unconnected-(H2-Pad11)") (class "Default")
      (node (ref "H2") (pin "11") (pinfunction "11_11") (pintype "unspecified+no_connect"))
    )
    (net (code "67") (name "unconnected-(H2-Pad13)") (class "Default")
      (node (ref "H2") (pin "13") (pinfunction "13_13") (pintype "unspecified+no_connect"))
    )
    (net (code "68") (name "unconnected-(H2-Pad14)") (class "Default")
      (node (ref "H2") (pin "14") (pinfunction "14_14") (pintype "unspecified+no_connect"))
    )
    (net (code "69") (name "unconnected-(H2-Pad15)") (class "Default")
      (node (ref "H2") (pin "15") (pinfunction "15_15") (pintype "unspecified+no_connect"))
    )
    (net (code "70") (name "unconnected-(H2-Pad16)") (class "Default")
      (node (ref "H2") (pin "16") (pinfunction "16_16") (pintype "unspecified+no_connect"))
    )
    (net (code "71") (name "unconnected-(U7-COMP-Pad5)") (class "Default")
      (node (ref "U7") (pin "5") (pinfunction "COMP_5") (pintype "input+no_connect"))
    )
  )
)
